# module_base.net
KiCad netlist of a schematic drawn in Altium Designer
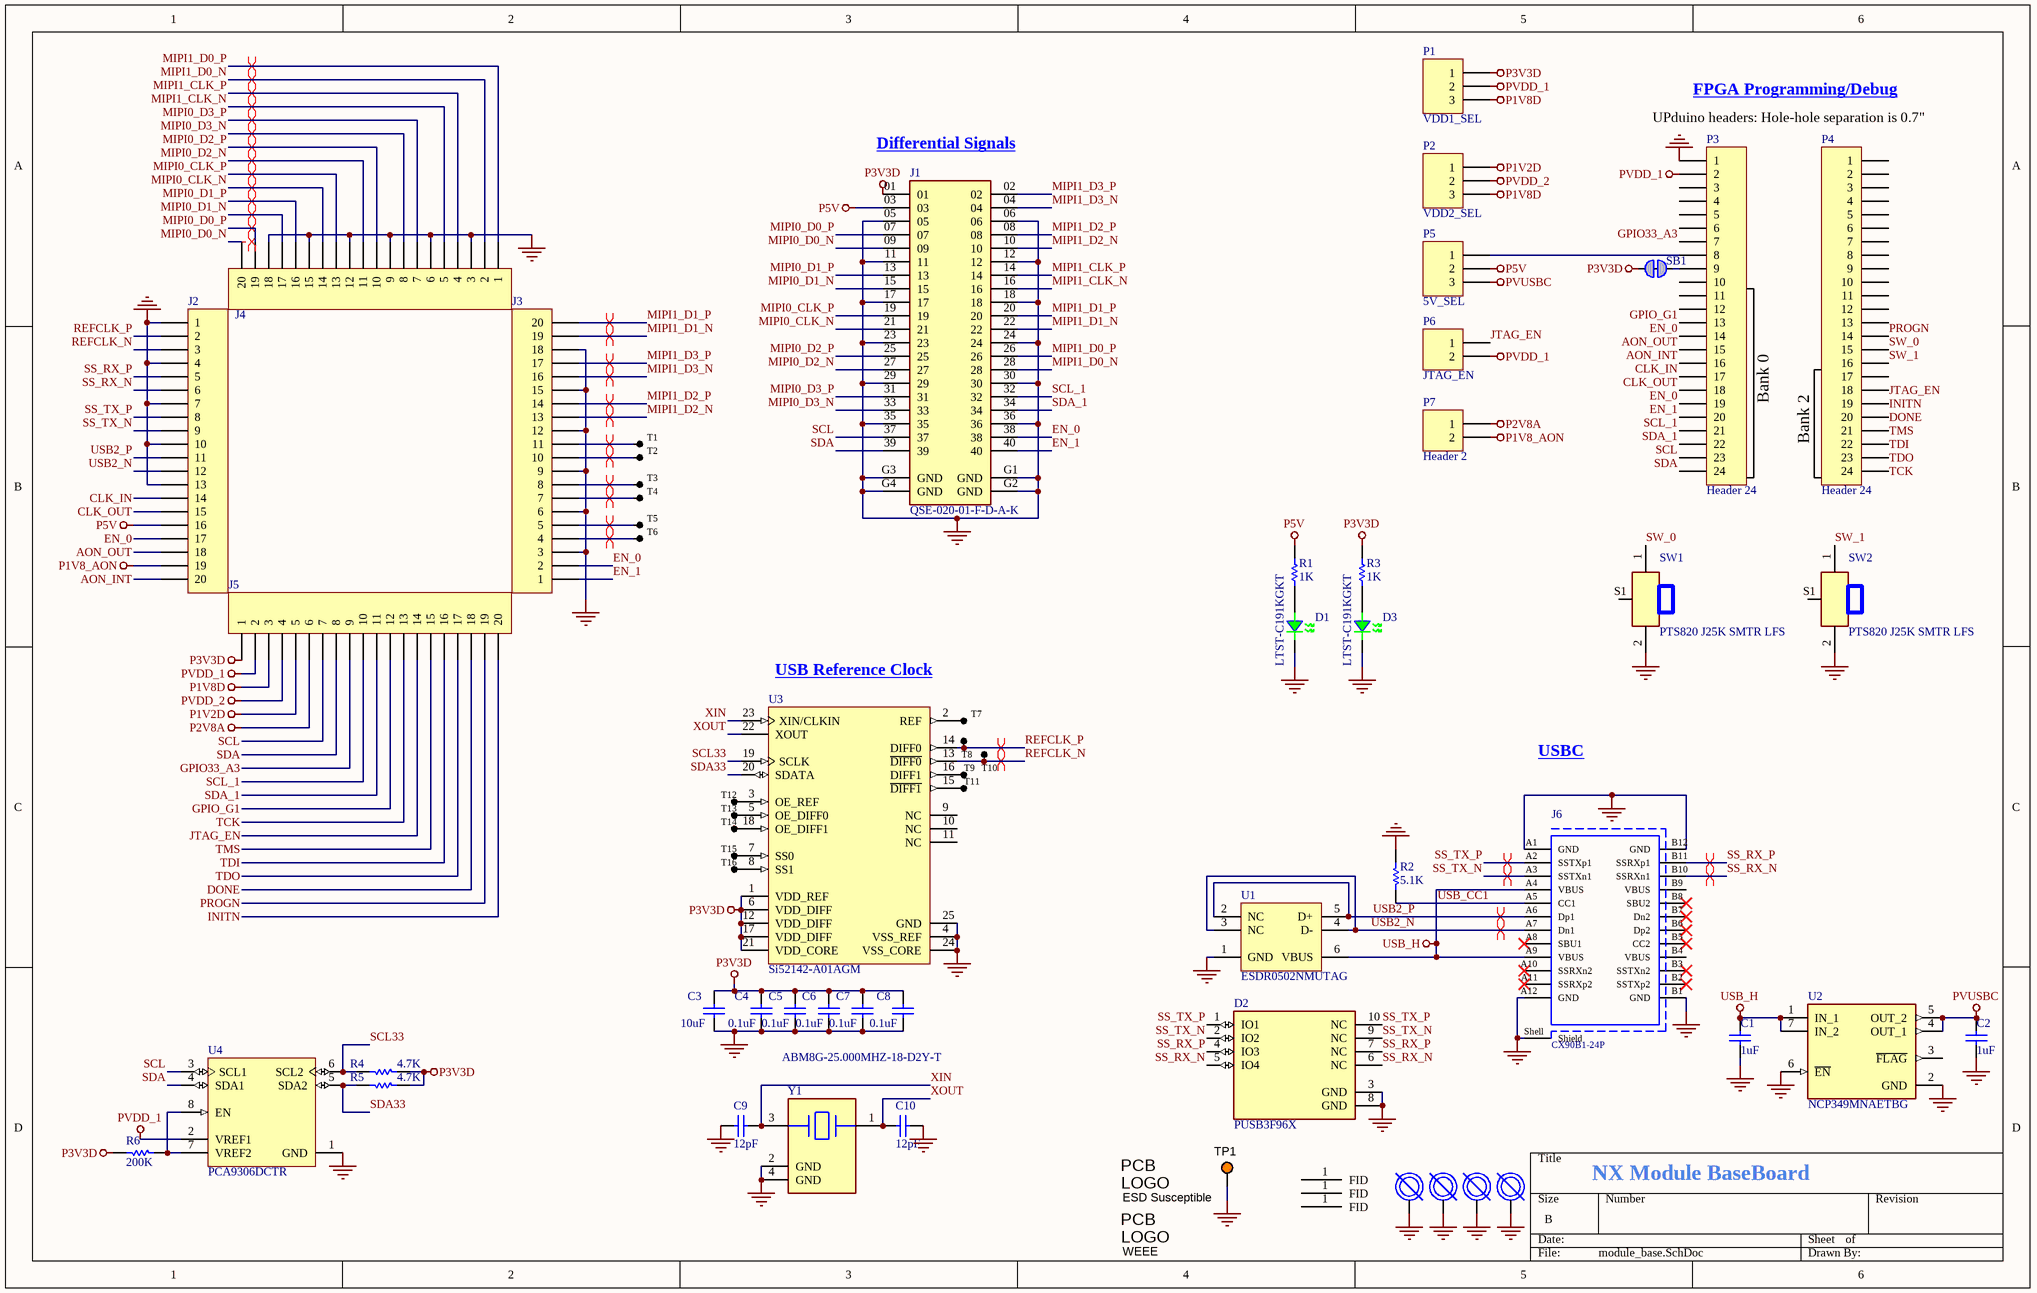
[diagram p0: module_base.SchDoc]

(export (version "E")
  (design (tool "Eeschema 10.0.6"))
  (components
    (comp (ref "BH1")
      (value "STANDOFF M2.5")
      (footprint "WE_9774010243R")
      (description "ROUND STANDOFF M2X0.4 STEEL 1MM")
      (fields
        (field (name "MANUFACTURER PART NUMBER") "9774010243R")
        (field (name "MANUFACTURER") "Würth Elektronik")
      )
      (libsource (lib "MIPI_xlator") (part "MOUNT_HOLE"))
    )
    (comp (ref "BH2")
      (value "STANDOFF M2.5")
      (footprint "WE_9774010243R")
      (description "ROUND STANDOFF M2X0.4 STEEL 1MM")
      (fields
        (field (name "MANUFACTURER PART NUMBER") "9774010243R")
        (field (name "MANUFACTURER") "Würth Elektronik")
      )
      (libsource (lib "MIPI_xlator") (part "MOUNT_HOLE"))
    )
    (comp (ref "BH3")
      (value "STANDOFF M2.5")
      (footprint "WE_9774010243R")
      (description "ROUND STANDOFF M2X0.4 STEEL 1MM")
      (fields
        (field (name "MANUFACTURER PART NUMBER") "9774010243R")
        (field (name "MANUFACTURER") "Würth Elektronik")
      )
      (libsource (lib "MIPI_xlator") (part "MOUNT_HOLE"))
    )
    (comp (ref "BH4")
      (value "STANDOFF M2.5")
      (footprint "WE_9774010243R")
      (description "ROUND STANDOFF M2X0.4 STEEL 1MM")
      (fields
        (field (name "MANUFACTURER PART NUMBER") "9774010243R")
        (field (name "MANUFACTURER") "Würth Elektronik")
      )
      (libsource (lib "MIPI_xlator") (part "MOUNT_HOLE"))
    )
    (comp (ref "C1")
      (value "1uF")
      (footprint "CAPC1005X55USR")
      (description "CAP CER 1UF 25V X5R 0402")
      (fields
        (field (name "MANUFACTURER PART NUMBER") "GRM155R61E105MA12D")
        (field (name "MANUFACTURER") "Murata Electronics")
      )
      (libsource (lib "Tiger_Ti180") (part "CAP CER 1UF 25V X5R 0402"))
    )
    (comp (ref "C2")
      (value "1uF")
      (footprint "CAPC1005X55USR")
      (description "CAP CER 1UF 25V X5R 0402")
      (fields
        (field (name "MANUFACTURER PART NUMBER") "GRM155R61E105MA12D")
        (field (name "MANUFACTURER") "Murata Electronics")
      )
      (libsource (lib "Tiger_Ti180") (part "CAP CER 1UF 25V X5R 0402"))
    )
    (comp (ref "C3")
      (value "10uF")
      (footprint "CAPC1005X90")
      (description "CAP CER 10UF 10V X5R 0402")
      (fields
        (field (name "MANUFACTURER PART NUMBER") "CL05A106MP8NUB8")
        (field (name "MANUFACTURER") "Samsung Electro-Mechanics")
      )
      (libsource (lib "Smart Camera") (part "Cap_1uF_X5R_10%_6V3_0402"))
    )
    (comp (ref "C4")
      (value "0.1uF")
      (footprint "CAPC0603X33N")
      (description "CAP CER 0.1UF 10V X7S 0201")
      (fields
        (field (name "MANUFACTURER PART NUMBER") "C0603X7S1A104K030BC")
        (field (name "MANUFACTURER") "TDK Corporation")
      )
      (libsource (lib "Smart Camera v2") (part "CAP CER 0.1UF 10V X7S 0201"))
    )
    (comp (ref "C5")
      (value "0.1uF")
      (footprint "CAPC0603X33N")
      (description "CAP CER 0.1UF 10V X7S 0201")
      (fields
        (field (name "MANUFACTURER PART NUMBER") "C0603X7S1A104K030BC")
        (field (name "MANUFACTURER") "TDK Corporation")
      )
      (libsource (lib "Smart Camera v2") (part "CAP CER 0.1UF 10V X7S 0201"))
    )
    (comp (ref "C6")
      (value "0.1uF")
      (footprint "CAPC0603X33N")
      (description "CAP CER 0.1UF 10V X7S 0201")
      (fields
        (field (name "MANUFACTURER PART NUMBER") "C0603X7S1A104K030BC")
        (field (name "MANUFACTURER") "TDK Corporation")
      )
      (libsource (lib "Smart Camera v2") (part "CAP CER 0.1UF 10V X7S 0201"))
    )
    (comp (ref "C7")
      (value "0.1uF")
      (footprint "CAPC0603X33N")
      (description "CAP CER 0.1UF 10V X7S 0201")
      (fields
        (field (name "MANUFACTURER PART NUMBER") "C0603X7S1A104K030BC")
        (field (name "MANUFACTURER") "TDK Corporation")
      )
      (libsource (lib "Smart Camera v2") (part "CAP CER 0.1UF 10V X7S 0201"))
    )
    (comp (ref "C8")
      (value "0.1uF")
      (footprint "CAPC0603X33N")
      (description "CAP CER 0.1UF 10V X7S 0201")
      (fields
        (field (name "MANUFACTURER PART NUMBER") "C0603X7S1A104K030BC")
        (field (name "MANUFACTURER") "TDK Corporation")
      )
      (libsource (lib "Smart Camera v2") (part "CAP CER 0.1UF 10V X7S 0201"))
    )
    (comp (ref "C9")
      (value "12pF")
      (footprint "CAPC0603X33N")
      (description "CAP CER 12PF 50V C0G 0201")
      (fields
        (field (name "MANUFACTURER PART NUMBER") "C0603C0G1H120K030BA")
        (field (name "MANUFACTURER") "TDK Corporation")
      )
      (libsource (lib "tinyAI") (part "CAP CER 12PF 50V C0G 0201"))
    )
    (comp (ref "C10")
      (value "12pF")
      (footprint "CAPC0603X33N")
      (description "CAP CER 12PF 50V C0G 0201")
      (fields
        (field (name "MANUFACTURER PART NUMBER") "C0603C0G1H120K030BA")
        (field (name "MANUFACTURER") "TDK Corporation")
      )
      (libsource (lib "tinyAI") (part "CAP CER 12PF 50V C0G 0201"))
    )
    (comp (ref "D1")
      (value "LTST-C191KGKT")
      (footprint "LED_0603")
      (description "LED GREEN CLEAR CHIP 0603 SMD")
      (fields
        (field (name "MANUFACTURER") "Lite-On Inc.")
        (field (name "MANUFACTURER PART NUMBER") "LTST-C191GKT")
      )
      (libsource (lib "Tiger_Ti180") (part "0603LED_GRN"))
    )
    (comp (ref "D2")
      (value "PUSB3F96X")
      (footprint "DFN2510A-10")
      (description "TVS DIODE 5.5VWM 4.6VC DFN2510A")
      (fields (field (name "MANUFACTURER") "Nexperia USA Inc."))
      (libsource (lib "Tiger_Ti180") (part "PUSB3F96X"))
    )
    (comp (ref "D3")
      (value "LTST-C191KGKT")
      (footprint "LED_0603")
      (description "LED GREEN CLEAR CHIP 0603 SMD")
      (fields
        (field (name "MANUFACTURER") "Lite-On Inc.")
        (field (name "MANUFACTURER PART NUMBER") "LTST-C191GKT")
      )
      (libsource (lib "Tiger_Ti180") (part "0603LED_GRN"))
    )
    (comp (ref "FID1") (value "~") (footprint "FID_040") (libsource (lib "MIPI_xlator") (part "FID")))
    (comp (ref "FID2") (value "~") (footprint "FID_040") (libsource (lib "MIPI_xlator") (part "FID")))
    (comp (ref "FID3") (value "~") (footprint "FID_040") (libsource (lib "MIPI_xlator") (part "FID")))
    (comp (ref "J1")
      (value "QSE-020-01-F-D-A-K")
      (footprint "SAMTEC_QSE-020-01-XXX-D-A-L")
      (description "Q Strip® High-Speed Ground Plane Header, 0.80mm Pitch")
      (fields
        (field (name "MANUFACTURER") "Samtec")
        (field (name "MANUFACTURER PART NUMBER") "QTE-020-01-F-D-A")
      )
      (libsource (lib "NX Module baseboard") (part "QSE-020-01-F-D-A-K"))
    )
    (comp (ref "J2")
      (value "Header 20")
      (footprint "HDR1X20_CASTELLATED")
      (description "Header, 20-Pin")
      (fields (field (name "PUBLISHER") "Altium Limited"))
      (libsource (lib "") (part "Header 20_2"))
    )
    (comp (ref "J3")
      (value "Header 20")
      (footprint "HDR1X20_CASTELLATED")
      (description "Header, 20-Pin")
      (fields (field (name "PUBLISHER") "Altium Limited"))
      (libsource (lib "") (part "Header 20_1"))
    )
    (comp (ref "J4")
      (value "Header 20")
      (footprint "HDR1X20_CASTELLATED")
      (description "Header, 20-Pin")
      (fields (field (name "PUBLISHER") "Altium Limited"))
      (libsource (lib "") (part "Header 20_3"))
    )
    (comp (ref "J5")
      (value "Header 20")
      (footprint "HDR1X20_CASTELLATED")
      (description "Header, 20-Pin")
      (fields (field (name "PUBLISHER") "Altium Limited"))
      (libsource (lib "NX Module") (part "Header 20"))
    )
    (comp (ref "J6")
      (value "CX90B1-24P")
      (footprint "HRS_CX90B1-24P")
      (description "CONN RCP USB3.1 TYPEC 24P SMD RA")
      (fields (field (name "MANUFACTURER") "Hirose Electric Co Ltd"))
      (libsource (lib "Tiger_Ti180") (part "USB 3.1_HRS_CX90B1-24P"))
    )
    (comp (ref "Logo1")
      (value "WEEE")
      (footprint "WEEE_Minimum")
      (description "WEEE logo")
      (libsource (lib "MIPI_xlator") (part "Logo WEEE"))
    )
    (comp (ref "Logo2")
      (value "ESD Susceptible")
      (footprint "ESD_Overlay_Medium")
      (description "ESD Susceptible Symbol")
      (fields (field (name "PUBLISHER") "Texas Instruments") (field (name "SYMBOLCREATOR") "a0412235"))
      (libsource (lib "MIPI_xlator") (part "Logo ESD"))
    )
    (comp (ref "P1")
      (value "VDD1_SEL")
      (footprint "HDR1X3")
      (description "Header, 3-Pin")
      (fields (field (name "PUBLISHER") "Altium Limited"))
      (libsource (lib "Miscellaneous Connectors") (part "Header 3"))
    )
    (comp (ref "P2")
      (value "VDD2_SEL")
      (footprint "HDR1X3")
      (description "Header, 3-Pin")
      (fields (field (name "PUBLISHER") "Altium Limited"))
      (libsource (lib "Miscellaneous Connectors") (part "Header 3"))
    )
    (comp (ref "P3")
      (value "Header 24")
      (footprint "HDR1X24")
      (description "Header, 24-Pin")
      (fields (field (name "PUBLISHER") "Altium Limited"))
      (libsource (lib "") (part "Header 24_1"))
    )
    (comp (ref "P4")
      (value "Header 24")
      (footprint "HDR1X24")
      (description "Header, 24-Pin")
      (fields (field (name "PUBLISHER") "Altium Limited"))
      (libsource (lib "Miscellaneous Connectors") (part "Header 24"))
    )
    (comp (ref "P5")
      (value "5V_SEL")
      (footprint "HDR1X3")
      (description "Header, 3-Pin")
      (fields (field (name "PUBLISHER") "Altium Limited"))
      (libsource (lib "Miscellaneous Connectors") (part "Header 3"))
    )
    (comp (ref "P6")
      (value "JTAG_EN")
      (footprint "HDR1X2")
      (description "Header, 2-Pin")
      (fields (field (name "PUBLISHER") "Altium Limited"))
      (libsource (lib "Miscellaneous Connectors") (part "Header 2"))
    )
    (comp (ref "P7")
      (value "Header 2")
      (footprint "HDR1X2")
      (description "Header, 2-Pin")
      (fields (field (name "PUBLISHER") "Altium Limited"))
      (libsource (lib "Miscellaneous Connectors") (part "Header 2"))
    )
    (comp (ref "R1")
      (value "1K")
      (footprint "RESC1005X40USR")
      (description "RES SMD 1K OHM 1% 1/16W 0402")
      (fields
        (field (name "MANUFACTURER") "YAGEO")
        (field (name "MANUFACTURER PART NUMBER") "RC0402FR-071KL")
      )
      (libsource (lib "Tiger_Ti180") (part "RES 1K OHM 1% 1/16W 0402"))
    )
    (comp (ref "R2")
      (value "5.1K")
      (footprint "RESC1005X40USR")
      (description "RES SMD 5.1K OHM 1% 1/16W 0402")
      (fields
        (field (name "MANUFACTURER") "YAGEO")
        (field (name "MANUFACTURER PART NUMBER") "RC0402FR-075K1L")
      )
      (libsource (lib "Tiger_Ti180") (part "RES 5.1K OHM 1% 1/16W 0402"))
    )
    (comp (ref "R3")
      (value "1K")
      (footprint "RESC1005X40USR")
      (description "RES SMD 1K OHM 1% 1/16W 0402")
      (fields
        (field (name "MANUFACTURER") "YAGEO")
        (field (name "MANUFACTURER PART NUMBER") "RC0402FR-071KL")
      )
      (libsource (lib "Tiger_Ti180") (part "RES 1K OHM 1% 1/16W 0402"))
    )
    (comp (ref "R4")
      (value "4.7K")
      (footprint "RESC0603X26N")
      (description "RES 4.7K OHM 1% 1/20W 0201")
      (fields
        (field (name "MANUFACTURER") "Yageo")
        (field (name "MANUFACTURER PART NUMBER") "RC0201FR-074K7L")
      )
      (libsource (lib "Smart Camera v2") (part "RES 4.7K OHM 1% 1/20W 0201"))
    )
    (comp (ref "R5")
      (value "4.7K")
      (footprint "RESC0603X26N")
      (description "RES 4.7K OHM 1% 1/20W 0201")
      (fields
        (field (name "MANUFACTURER") "Yageo")
        (field (name "MANUFACTURER PART NUMBER") "RC0201FR-074K7L")
      )
      (libsource (lib "Smart Camera v2") (part "RES 4.7K OHM 1% 1/20W 0201"))
    )
    (comp (ref "R6")
      (value "200K")
      (footprint "RESC1005X40USR")
      (description "RES SMD 200K OHM 1% 1/16W 0402")
      (fields
        (field (name "MANUFACTURER") "Stackpole Electronics Inc")
        (field (name "MANUFACTURER PART NUMBER") "RMCF0402FT200K")
      )
      (libsource (lib "MCD_Temp_LBE") (part "Res_10K_1%_0402"))
    )
    (comp (ref "SB1")
      (value "Solderbridge")
      (footprint "Solderbridge_Shorted")
      (description "Shorted Solderbridge")
      (fields
        (field (name "PART NUMBER") "Solderbridge Shorted")
        (field (name "PUBLISHER") "Nordic Semiconductor")
      )
      (libsource (lib "Tiger_Ti180") (part "Solderbridge Shorted"))
    )
    (comp (ref "SW1")
      (value "PTS820 J25K SMTR LFS")
      (footprint "PTS820J25MSMTRLFS")
      (description "SWITCH TACTILE SPST-NO 0.05A 12V")
      (fields (field (name "MANUFACTURER") "C&K"))
      (libsource (lib "Tiger_Ti180") (part "SPST_NO"))
    )
    (comp (ref "SW2")
      (value "PTS820 J25K SMTR LFS")
      (footprint "PTS820J25MSMTRLFS")
      (description "SWITCH TACTILE SPST-NO 0.05A 12V")
      (fields (field (name "MANUFACTURER") "C&K"))
      (libsource (lib "Tiger_Ti180") (part "SPST_NO"))
    )
    (comp (ref "T1")
      (value "~")
      (footprint "TP 1mm")
      (description "test point")
      (libsource (lib "Smart Camera") (part "TP_S"))
    )
    (comp (ref "T2")
      (value "~")
      (footprint "TP 1mm")
      (description "test point")
      (libsource (lib "Smart Camera") (part "TP_S"))
    )
    (comp (ref "T3")
      (value "~")
      (footprint "TP 1mm")
      (description "test point")
      (libsource (lib "Smart Camera") (part "TP_S"))
    )
    (comp (ref "T4")
      (value "~")
      (footprint "TP 1mm")
      (description "test point")
      (libsource (lib "Smart Camera") (part "TP_S"))
    )
    (comp (ref "T5")
      (value "~")
      (footprint "TP 1mm")
      (description "test point")
      (libsource (lib "Smart Camera") (part "TP_S"))
    )
    (comp (ref "T6")
      (value "~")
      (footprint "TP 1mm")
      (description "test point")
      (libsource (lib "Smart Camera") (part "TP_S"))
    )
    (comp (ref "T7")
      (value "~")
      (footprint "TP 1mm")
      (description "test point")
      (libsource (lib "Smart Camera") (part "TP_S"))
    )
    (comp (ref "T8")
      (value "~")
      (footprint "TP 1mm")
      (description "test point")
      (libsource (lib "Smart Camera") (part "TP_S"))
    )
    (comp (ref "T9")
      (value "~")
      (footprint "TP 1mm")
      (description "test point")
      (libsource (lib "Smart Camera") (part "TP_S"))
    )
    (comp (ref "T10")
      (value "~")
      (footprint "TP 1mm")
      (description "test point")
      (libsource (lib "Smart Camera") (part "TP_S"))
    )
    (comp (ref "T11")
      (value "~")
      (footprint "TP 1mm")
      (description "test point")
      (libsource (lib "Smart Camera") (part "TP_S"))
    )
    (comp (ref "T12")
      (value "~")
      (footprint "TP 1mm")
      (description "test point")
      (libsource (lib "Smart Camera") (part "TP_S"))
    )
    (comp (ref "T13")
      (value "~")
      (footprint "TP 1mm")
      (description "test point")
      (libsource (lib "Smart Camera") (part "TP_S"))
    )
    (comp (ref "T14")
      (value "~")
      (footprint "TP 1mm")
      (description "test point")
      (libsource (lib "Smart Camera") (part "TP_S"))
    )
    (comp (ref "T15")
      (value "~")
      (footprint "TP 1mm")
      (description "test point")
      (libsource (lib "Smart Camera") (part "TP_S"))
    )
    (comp (ref "T16")
      (value "~")
      (footprint "TP 1mm")
      (description "test point")
      (libsource (lib "Smart Camera") (part "TP_S"))
    )
    (comp (ref "TP1")
      (value "5019")
      (footprint "TP380X203")
      (description "PC TEST POINT MINIATURE")
      (fields (field (name "MANUFACTURER") "Keystone Electronics"))
      (libsource (lib "MIPI_xlator") (part "5019"))
    )
    (comp (ref "U1")
      (value "ESDR0502NMUTAG")
      (footprint "ONSC-UDFN-6-517AA-01_V")
      (description "TVS DIODE 5.5VWM 6UDFN")
      (fields (field (name "MANUFACTURER") "ON Semiconductor"))
      (libsource (lib "Tiger_Ti180") (part "ONSC-ESDR0502N-UDFN-6-517AA-01"))
    )
    (comp (ref "U2")
      (value "NCP349MNAETBG")
      (footprint "SON50P200X160X100-7N-D")
      (description "IC CTLR OVP 28V W/NMOS 6-DFN")
      (fields (field (name "MANUFACTURER") "ON Semiconductor"))
      (libsource (lib "Tiger_Ti180") (part "NCP349MNAETBG"))
    )
    (comp (ref "U3")
      (value "Si52142-A01AGM")
      (footprint "SLAB-QFN-24-2700x2700TP_M")
      (fields (field (name "MANUFACTURER") "Silicon Labs"))
      (libsource (lib "Altium Content Vault") (part "SLAB-Si52142-QFN-24-25"))
    )
    (comp (ref "U4")
      (value "PCA9306DCTR")
      (footprint "SOP65P400X130-8N")
      (fields (field (name "MANUFACTURER") "Texas Instruments"))
      (libsource (lib "NX Module") (part "TI-PCA9306-SM8_DCT-8"))
    )
    (comp (ref "Y1")
      (value "ABM8G-25.000MHZ-18-D2Y-T")
      (footprint "XTAL_ABM8G3225X10")
      (description "Crystal 25MHz ±20ppm (Tol) ±30ppm (Stability) 18pF FUND 60Ohm 4-Pin Ultra Mini-CSMD T/R")
      (fields (field (name "MANUFACTURER") "Abracon") (field (name "TOLERANCE") "20ppm"))
      (libsource (lib "NX Module") (part "48e526d86b7f2615d98721063c72f49"))
    )
  )
  (nets
    (net (code "1") (name "/AON_INT") (class "Default")
      (node (ref "J2") (pin "20") (pinfunction "20_20") (pintype "passive"))
      (node (ref "P3") (pin "16") (pinfunction "16_16") (pintype "passive"))
    )
    (net (code "2") (name "/AON_OUT") (class "Default")
      (node (ref "J2") (pin "18") (pinfunction "18_18") (pintype "passive"))
      (node (ref "P3") (pin "15") (pinfunction "15_15") (pintype "passive"))
    )
    (net (code "3") (name "/CLK_IN") (class "Default")
      (node (ref "J2") (pin "14") (pinfunction "14_14") (pintype "passive"))
      (node (ref "P3") (pin "17") (pinfunction "17_17") (pintype "passive"))
    )
    (net (code "4") (name "/CLK_OUT") (class "Default")
      (node (ref "J2") (pin "15") (pinfunction "15_15") (pintype "passive"))
      (node (ref "P3") (pin "18") (pinfunction "18_18") (pintype "passive"))
    )
    (net (code "5") (name "/DONE") (class "Default")
      (node (ref "J5") (pin "18") (pinfunction "18_18") (pintype "passive"))
      (node (ref "P4") (pin "20") (pinfunction "20_20") (pintype "passive"))
    )
    (net (code "6") (name "/EN_0") (class "Default")
      (node (ref "J1") (pin "38") (pinfunction "38_38") (pintype "passive"))
      (node (ref "J2") (pin "17") (pinfunction "17_17") (pintype "passive"))
      (node (ref "J3") (pin "2") (pinfunction "2_2") (pintype "passive"))
      (node (ref "P3") (pin "14") (pinfunction "14_14") (pintype "passive"))
      (node (ref "P3") (pin "19") (pinfunction "19_19") (pintype "passive"))
    )
    (net (code "7") (name "/EN_1") (class "Default")
      (node (ref "J1") (pin "40") (pinfunction "40_40") (pintype "passive"))
      (node (ref "J3") (pin "1") (pinfunction "1_1") (pintype "passive"))
      (node (ref "P3") (pin "20") (pinfunction "20_20") (pintype "passive"))
    )
    (net (code "8") (name "/GPIO33_A3") (class "Default")
      (node (ref "J5") (pin "9") (pinfunction "9_9") (pintype "passive"))
      (node (ref "P3") (pin "7") (pinfunction "7_7") (pintype "passive"))
    )
    (net (code "9") (name "/GPIO_G1") (class "Default")
      (node (ref "J5") (pin "12") (pinfunction "12_12") (pintype "passive"))
      (node (ref "P3") (pin "13") (pinfunction "13_13") (pintype "passive"))
    )
    (net (code "10") (name "/INITN") (class "Default")
      (node (ref "J5") (pin "20") (pinfunction "20_20") (pintype "passive"))
      (node (ref "P4") (pin "19") (pinfunction "19_19") (pintype "passive"))
    )
    (net (code "11") (name "/JTAG_EN") (class "Default")
      (node (ref "J5") (pin "14") (pinfunction "14_14") (pintype "passive"))
      (node (ref "P4") (pin "18") (pinfunction "18_18") (pintype "passive"))
      (node (ref "P6") (pin "1") (pinfunction "1_1") (pintype "passive"))
    )
    (net (code "12") (name "/MIPI0_CLK_N") (class "Default")
      (node (ref "J1") (pin "21") (pinfunction "21_21") (pintype "passive"))
      (node (ref "J4") (pin "14") (pinfunction "14_14") (pintype "passive"))
    )
    (net (code "13") (name "/MIPI0_CLK_P") (class "Default")
      (node (ref "J1") (pin "19") (pinfunction "19_19") (pintype "passive"))
      (node (ref "J4") (pin "13") (pinfunction "13_13") (pintype "passive"))
    )
    (net (code "14") (name "/MIPI0_D0_N") (class "Default")
      (node (ref "J1") (pin "09") (pinfunction "09_09") (pintype "passive"))
      (node (ref "J4") (pin "20") (pinfunction "20_20") (pintype "passive"))
    )
    (net (code "15") (name "/MIPI0_D0_P") (class "Default")
      (node (ref "J1") (pin "07") (pinfunction "07_07") (pintype "passive"))
      (node (ref "J4") (pin "19") (pinfunction "19_19") (pintype "passive"))
    )
    (net (code "16") (name "/MIPI0_D1_N") (class "Default")
      (node (ref "J1") (pin "15") (pinfunction "15_15") (pintype "passive"))
      (node (ref "J4") (pin "17") (pinfunction "17_17") (pintype "passive"))
    )
    (net (code "17") (name "/MIPI0_D1_P") (class "Default")
      (node (ref "J1") (pin "13") (pinfunction "13_13") (pintype "passive"))
      (node (ref "J4") (pin "16") (pinfunction "16_16") (pintype "passive"))
    )
    (net (code "18") (name "/MIPI0_D2_N") (class "Default")
      (node (ref "J1") (pin "27") (pinfunction "27_27") (pintype "passive"))
      (node (ref "J4") (pin "11") (pinfunction "11_11") (pintype "passive"))
    )
    (net (code "19") (name "/MIPI0_D2_P") (class "Default")
      (node (ref "J1") (pin "25") (pinfunction "25_25") (pintype "passive"))
      (node (ref "J4") (pin "10") (pinfunction "10_10") (pintype "passive"))
    )
    (net (code "20") (name "/MIPI0_D3_N") (class "Default")
      (node (ref "J1") (pin "33") (pinfunction "33_33") (pintype "passive"))
      (node (ref "J4") (pin "8") (pinfunction "8_8") (pintype "passive"))
    )
    (net (code "21") (name "/MIPI0_D3_P") (class "Default")
      (node (ref "J1") (pin "31") (pinfunction "31_31") (pintype "passive"))
      (node (ref "J4") (pin "7") (pinfunction "7_7") (pintype "passive"))
    )
    (net (code "22") (name "/MIPI1_CLK_N") (class "Default")
      (node (ref "J1") (pin "16") (pinfunction "16_16") (pintype "passive"))
      (node (ref "J4") (pin "5") (pinfunction "5_5") (pintype "passive"))
    )
    (net (code "23") (name "/MIPI1_CLK_P") (class "Default")
      (node (ref "J1") (pin "14") (pinfunction "14_14") (pintype "passive"))
      (node (ref "J4") (pin "4") (pinfunction "4_4") (pintype "passive"))
    )
    (net (code "24") (name "/MIPI1_D0_N") (class "Default")
      (node (ref "J1") (pin "28") (pinfunction "28_28") (pintype "passive"))
      (node (ref "J4") (pin "2") (pinfunction "2_2") (pintype "passive"))
    )
    (net (code "25") (name "/MIPI1_D0_P") (class "Default")
      (node (ref "J1") (pin "26") (pinfunction "26_26") (pintype "passive"))
      (node (ref "J4") (pin "1") (pinfunction "1_1") (pintype "passive"))
    )
    (net (code "26") (name "/MIPI1_D1_N") (class "Default")
      (node (ref "J1") (pin "22") (pinfunction "22_22") (pintype "passive"))
      (node (ref "J3") (pin "19") (pinfunction "19_19") (pintype "passive"))
    )
    (net (code "27") (name "/MIPI1_D1_P") (class "Default")
      (node (ref "J1") (pin "20") (pinfunction "20_20") (pintype "passive"))
      (node (ref "J3") (pin "20") (pinfunction "20_20") (pintype "passive"))
    )
    (net (code "28") (name "/MIPI1_D2_N") (class "Default")
      (node (ref "J1") (pin "10") (pinfunction "10_10") (pintype "passive"))
      (node (ref "J3") (pin "13") (pinfunction "13_13") (pintype "passive"))
    )
    (net (code "29") (name "/MIPI1_D2_P") (class "Default")
      (node (ref "J1") (pin "08") (pinfunction "08_08") (pintype "passive"))
      (node (ref "J3") (pin "14") (pinfunction "14_14") (pintype "passive"))
    )
    (net (code "30") (name "/MIPI1_D3_N") (class "Default")
      (node (ref "J1") (pin "04") (pinfunction "04_04") (pintype "passive"))
      (node (ref "J3") (pin "16") (pinfunction "16_16") (pintype "passive"))
    )
    (net (code "31") (name "/MIPI1_D3_P") (class "Default")
      (node (ref "J1") (pin "02") (pinfunction "02_02") (pintype "passive"))
      (node (ref "J3") (pin "17") (pinfunction "17_17") (pintype "passive"))
    )
    (net (code "32") (name "/PROGN") (class "Default")
      (node (ref "J5") (pin "19") (pinfunction "19_19") (pintype "passive"))
      (node (ref "P4") (pin "14") (pinfunction "14_14") (pintype "passive"))
    )
    (net (code "33") (name "/REFCLK_N") (class "Default")
      (node (ref "J2") (pin "3") (pinfunction "3_3") (pintype "passive"))
      (node (ref "T10") (pin "1") (pintype "passive"))
      (node (ref "U3") (pin "13") (pinfunction "~{DIFF0}_13") (pintype "output"))
    )
    (net (code "34") (name "/REFCLK_P") (class "Default")
      (node (ref "J2") (pin "2") (pinfunction "2_2") (pintype "passive"))
      (node (ref "T8") (pin "1") (pintype "passive"))
      (node (ref "U3") (pin "14") (pinfunction "DIFF0_14") (pintype "output"))
    )
    (net (code "35") (name "/SCL") (class "Default")
      (node (ref "J1") (pin "37") (pinfunction "37_37") (pintype "passive"))
      (node (ref "J5") (pin "7") (pinfunction "7_7") (pintype "passive"))
      (node (ref "P3") (pin "23") (pinfunction "23_23") (pintype "passive"))
      (node (ref "U4") (pin "3") (pinfunction "SCL1_3") (pintype "bidirectional"))
    )
    (net (code "36") (name "/SCL33") (class "Default")
      (node (ref "R4") (pin "1") (pinfunction "1_1") (pintype "passive"))
      (node (ref "U3") (pin "19") (pinfunction "SCLK_19") (pintype "input"))
      (node (ref "U4") (pin "6") (pinfunction "SCL2_6") (pintype "bidirectional"))
    )
    (net (code "37") (name "/SCL_1") (class "Default")
      (node (ref "J1") (pin "32") (pinfunction "32_32") (pintype "passive"))
      (node (ref "J5") (pin "10") (pinfunction "10_10") (pintype "passive"))
      (node (ref "P3") (pin "21") (pinfunction "21_21") (pintype "passive"))
    )
    (net (code "38") (name "/SDA") (class "Default")
      (node (ref "J1") (pin "39") (pinfunction "39_39") (pintype "passive"))
      (node (ref "J5") (pin "8") (pinfunction "8_8") (pintype "passive"))
      (node (ref "P3") (pin "24") (pinfunction "24_24") (pintype "passive"))
      (node (ref "U4") (pin "4") (pinfunction "SDA1_4") (pintype "bidirectional"))
    )
    (net (code "39") (name "/SDA33") (class "Default")
      (node (ref "R5") (pin "1") (pinfunction "1_1") (pintype "passive"))
      (node (ref "U3") (pin "20") (pinfunction "SDATA_20") (pintype "bidirectional"))
      (node (ref "U4") (pin "5") (pinfunction "SDA2_5") (pintype "bidirectional"))
    )
    (net (code "40") (name "/SDA_1") (class "Default")
      (node (ref "J1") (pin "34") (pinfunction "34_34") (pintype "passive"))
      (node (ref "J5") (pin "11") (pinfunction "11_11") (pintype "passive"))
      (node (ref "P3") (pin "22") (pinfunction "22_22") (pintype "passive"))
    )
    (net (code "41") (name "/SS_RX_N") (class "Default")
      (node (ref "D2") (pin "5") (pinfunction "IO4_5") (pintype "bidirectional"))
      (node (ref "D2") (pin "6") (pinfunction "NC_6") (pintype "passive"))
      (node (ref "J2") (pin "6") (pinfunction "6_6") (pintype "passive"))
      (node (ref "J6") (pin "B10") (pinfunction "SSRXn1_B10") (pintype "passive"))
    )
    (net (code "42") (name "/SS_RX_P") (class "Default")
      (node (ref "D2") (pin "4") (pinfunction "IO3_4") (pintype "bidirectional"))
      (node (ref "D2") (pin "7") (pinfunction "NC_7") (pintype "passive"))
      (node (ref "J2") (pin "5") (pinfunction "5_5") (pintype "passive"))
      (node (ref "J6") (pin "B11") (pinfunction "SSRXp1_B11") (pintype "passive"))
    )
    (net (code "43") (name "/SS_TX_N") (class "Default")
      (node (ref "D2") (pin "2") (pinfunction "IO2_2") (pintype "bidirectional"))
      (node (ref "D2") (pin "9") (pinfunction "NC_9") (pintype "passive"))
      (node (ref "J2") (pin "9") (pinfunction "9_9") (pintype "passive"))
      (node (ref "J6") (pin "A3") (pinfunction "SSTXn1_A3") (pintype "passive"))
    )
    (net (code "44") (name "/SS_TX_P") (class "Default")
      (node (ref "D2") (pin "1") (pinfunction "IO1_1") (pintype "bidirectional"))
      (node (ref "D2") (pin "10") (pinfunction "NC_10") (pintype "passive"))
      (node (ref "J2") (pin "8") (pinfunction "8_8") (pintype "passive"))
      (node (ref "J6") (pin "A2") (pinfunction "SSTXp1_A2") (pintype "passive"))
    )
    (net (code "45") (name "/SW_0") (class "Default")
      (node (ref "P4") (pin "15") (pinfunction "15_15") (pintype "passive"))
      (node (ref "SW1") (pin "1") (pinfunction "1_1") (pintype "passive"))
    )
    (net (code "46") (name "/SW_1") (class "Default")
      (node (ref "P4") (pin "16") (pinfunction "16_16") (pintype "passive"))
      (node (ref "SW2") (pin "1") (pinfunction "1_1") (pintype "passive"))
    )
    (net (code "47") (name "/TCK") (class "Default")
      (node (ref "J5") (pin "13") (pinfunction "13_13") (pintype "passive"))
      (node (ref "P4") (pin "24") (pinfunction "24_24") (pintype "passive"))
    )
    (net (code "48") (name "/TDI") (class "Default")
      (node (ref "J5") (pin "16") (pinfunction "16_16") (pintype "passive"))
      (node (ref "P4") (pin "22") (pinfunction "22_22") (pintype "passive"))
    )
    (net (code "49") (name "/TDO") (class "Default")
      (node (ref "J5") (pin "17") (pinfunction "17_17") (pintype "passive"))
      (node (ref "P4") (pin "23") (pinfunction "23_23") (pintype "passive"))
    )
    (net (code "50") (name "/TMS") (class "Default")
      (node (ref "J5") (pin "15") (pinfunction "15_15") (pintype "passive"))
      (node (ref "P4") (pin "21") (pinfunction "21_21") (pintype "passive"))
    )
    (net (code "51") (name "/USB2_N") (class "Default")
      (node (ref "J2") (pin "12") (pinfunction "12_12") (pintype "passive"))
      (node (ref "J6") (pin "A7") (pinfunction "Dn1_A7") (pintype "passive"))
      (node (ref "U1") (pin "3") (pinfunction "NC_3") (pintype "passive"))
      (node (ref "U1") (pin "4") (pinfunction "D-_4") (pintype "passive"))
    )
    (net (code "52") (name "/USB2_P") (class "Default")
      (node (ref "J2") (pin "11") (pinfunction "11_11") (pintype "passive"))
      (node (ref "J6") (pin "A6") (pinfunction "Dp1_A6") (pintype "passive"))
      (node (ref "U1") (pin "2") (pinfunction "NC_2") (pintype "passive"))
      (node (ref "U1") (pin "5") (pinfunction "D+_5") (pintype "passive"))
    )
    (net (code "53") (name "/USB_CC1") (class "Default")
      (node (ref "J6") (pin "A5") (pinfunction "CC1_A5") (pintype "passive"))
      (node (ref "R2") (pin "1") (pinfunction "1_1") (pintype "passive"))
    )
    (net (code "54") (name "/XIN") (class "Default")
      (node (ref "C9") (pin "1") (pinfunction "1_1") (pintype "passive"))
      (node (ref "U3") (pin "23") (pinfunction "XIN/CLKIN_23") (pintype "input"))
      (node (ref "Y1") (pin "3") (pinfunction "3_3") (pintype "passive"))
    )
    (net (code "55") (name "/XOUT") (class "Default")
      (node (ref "C10") (pin "1") (pinfunction "1_1") (pintype "passive"))
      (node (ref "U3") (pin "22") (pinfunction "XOUT_22") (pintype "passive"))
      (node (ref "Y1") (pin "1") (pinfunction "1_1") (pintype "passive"))
    )
    (net (code "56") (name "GND") (class "Default")
      (node (ref "BH1") (pin "1") (pinfunction "1_1") (pintype "passive"))
      (node (ref "BH2") (pin "1") (pinfunction "1_1") (pintype "passive"))
      (node (ref "BH3") (pin "1") (pinfunction "1_1") (pintype "passive"))
      (node (ref "BH4") (pin "1") (pinfunction "1_1") (pintype "passive"))
      (node (ref "C1") (pin "1") (pinfunction "1_1") (pintype "passive"))
      (node (ref "C10") (pin "2") (pinfunction "2_2") (pintype "passive"))
      (node (ref "C2") (pin "1") (pinfunction "1_1") (pintype "passive"))
      (node (ref "C3") (pin "1") (pinfunction "1_1") (pintype "passive"))
      (node (ref "C4") (pin "1") (pinfunction "1_1") (pintype "passive"))
      (node (ref "C5") (pin "1") (pinfunction "1_1") (pintype "passive"))
      (node (ref "C6") (pin "1") (pinfunction "1_1") (pintype "passive"))
      (node (ref "C7") (pin "1") (pinfunction "1_1") (pintype "passive"))
      (node (ref "C8") (pin "1") (pinfunction "1_1") (pintype "passive"))
      (node (ref "C9") (pin "2") (pinfunction "2_2") (pintype "passive"))
      (node (ref "D1") (pin "2") (pinfunction "K_2") (pintype "passive"))
      (node (ref "D2") (pin "3") (pinfunction "GND_3") (pintype "power_in"))
      (node (ref "D2") (pin "8") (pinfunction "GND_8") (pintype "power_in"))
      (node (ref "D3") (pin "2") (pinfunction "K_2") (pintype "passive"))
      (node (ref "J1") (pin "05") (pinfunction "05_05") (pintype "passive"))
      (node (ref "J1") (pin "06") (pinfunction "06_06") (pintype "passive"))
      (node (ref "J1") (pin "11") (pinfunction "11_11") (pintype "passive"))
      (node (ref "J1") (pin "12") (pinfunction "12_12") (pintype "passive"))
      (node (ref "J1") (pin "17") (pinfunction "17_17") (pintype "passive"))
      (node (ref "J1") (pin "18") (pinfunction "18_18") (pintype "passive"))
      (node (ref "J1") (pin "23") (pinfunction "23_23") (pintype "passive"))
      (node (ref "J1") (pin "24") (pinfunction "24_24") (pintype "passive"))
      (node (ref "J1") (pin "29") (pinfunction "29_29") (pintype "passive"))
      (node (ref "J1") (pin "30") (pinfunction "30_30") (pintype "passive"))
      (node (ref "J1") (pin "35") (pinfunction "35_35") (pintype "passive"))
      (node (ref "J1") (pin "36") (pinfunction "36_36") (pintype "passive"))
      (node (ref "J1") (pin "G1") (pinfunction "GND_G1") (pintype "power_in"))
      (node (ref "J1") (pin "G2") (pinfunction "GND_G2") (pintype "power_in"))
      (node (ref "J1") (pin "G3") (pinfunction "GND_G3") (pintype "power_in"))
      (node (ref "J1") (pin "G4") (pinfunction "GND_G4") (pintype "power_in"))
      (node (ref "J2") (pin "1") (pinfunction "1_1") (pintype "passive"))
      (node (ref "J2") (pin "10") (pinfunction "10_10") (pintype "passive"))
      (node (ref "J2") (pin "13") (pinfunction "13_13") (pintype "passive"))
      (node (ref "J2") (pin "4") (pinfunction "4_4") (pintype "passive"))
      (node (ref "J2") (pin "7") (pinfunction "7_7") (pintype "passive"))
      (node (ref "J3") (pin "12") (pinfunction "12_12") (pintype "passive"))
      (node (ref "J3") (pin "15") (pinfunction "15_15") (pintype "passive"))
      (node (ref "J3") (pin "18") (pinfunction "18_18") (pintype "passive"))
      (node (ref "J3") (pin "3") (pinfunction "3_3") (pintype "passive"))
      (node (ref "J3") (pin "6") (pinfunction "6_6") (pintype "passive"))
      (node (ref "J3") (pin "9") (pinfunction "9_9") (pintype "passive"))
      (node (ref "J4") (pin "12") (pinfunction "12_12") (pintype "passive"))
      (node (ref "J4") (pin "15") (pinfunction "15_15") (pintype "passive"))
      (node (ref "J4") (pin "18") (pinfunction "18_18") (pintype "passive"))
      (node (ref "J4") (pin "3") (pinfunction "3_3") (pintype "passive"))
      (node (ref "J4") (pin "6") (pinfunction "6_6") (pintype "passive"))
      (node (ref "J4") (pin "9") (pinfunction "9_9") (pintype "passive"))
      (node (ref "J6") (pin "A1") (pinfunction "GND_A1") (pintype "passive"))
      (node (ref "J6") (pin "A12") (pinfunction "GND_A12") (pintype "passive"))
      (node (ref "J6") (pin "B1") (pinfunction "GND_B1") (pintype "passive"))
      (node (ref "J6") (pin "B12") (pinfunction "GND_B12") (pintype "passive"))
      (node (ref "J6") (pin "Shell") (pinfunction "Shield_Shell") (pintype "passive"))
      (node (ref "P3") (pin "1") (pinfunction "1_1") (pintype "passive"))
      (node (ref "R2") (pin "2") (pinfunction "2_2") (pintype "passive"))
      (node (ref "SW1") (pin "2") (pinfunction "2_2") (pintype "passive"))
      (node (ref "SW2") (pin "2") (pinfunction "2_2") (pintype "passive"))
      (node (ref "TP1") (pin "1") (pinfunction "1_1") (pintype "passive"))
      (node (ref "U1") (pin "1") (pinfunction "GND_1") (pintype "power_in"))
      (node (ref "U2") (pin "2") (pinfunction "GND_2") (pintype "power_in"))
      (node (ref "U2") (pin "6") (pinfunction "~{EN}_6") (pintype "input"))
      (node (ref "U3") (pin "24") (pinfunction "VSS_CORE_24") (pintype "power_in"))
      (node (ref "U3") (pin "25") (pinfunction "GND_25") (pintype "power_in"))
      (node (ref "U3") (pin "4") (pinfunction "VSS_REF_4") (pintype "power_in"))
      (node (ref "U4") (pin "1") (pinfunction "GND_1") (pintype "power_in"))
      (node (ref "Y1") (pin "2") (pinfunction "GND_2") (pintype "power_in"))
      (node (ref "Y1") (pin "4") (pinfunction "GND_4") (pintype "power_in"))
    )
    (net (code "57") (name "Net-(D1-A)") (class "Default")
      (node (ref "D1") (pin "1") (pinfunction "A_1") (pintype "passive"))
      (node (ref "R1") (pin "2") (pinfunction "2_2") (pintype "passive"))
    )
    (net (code "58") (name "Net-(D3-A)") (class "Default")
      (node (ref "D3") (pin "1") (pinfunction "A_1") (pintype "passive"))
      (node (ref "R3") (pin "2") (pinfunction "2_2") (pintype "passive"))
    )
    (net (code "59") (name "Net-(J3-Pad4)") (class "Default")
      (node (ref "J3") (pin "4") (pinfunction "4_4") (pintype "passive"))
      (node (ref "T6") (pin "1") (pintype "passive"))
    )
    (net (code "60") (name "Net-(J3-Pad5)") (class "Default")
      (node (ref "J3") (pin "5") (pinfunction "5_5") (pintype "passive"))
      (node (ref "T5") (pin "1") (pintype "passive"))
    )
    (net (code "61") (name "Net-(J3-Pad7)") (class "Default")
      (node (ref "J3") (pin "7") (pinfunction "7_7") (pintype "passive"))
      (node (ref "T4") (pin "1") (pintype "passive"))
    )
    (net (code "62") (name "Net-(J3-Pad8)") (class "Default")
      (node (ref "J3") (pin "8") (pinfunction "8_8") (pintype "passive"))
      (node (ref "T3") (pin "1") (pintype "passive"))
    )
    (net (code "63") (name "Net-(J3-Pad10)") (class "Default")
      (node (ref "J3") (pin "10") (pinfunction "10_10") (pintype "passive"))
      (node (ref "T2") (pin "1") (pintype "passive"))
    )
    (net (code "64") (name "Net-(J3-Pad11)") (class "Default")
      (node (ref "J3") (pin "11") (pinfunction "11_11") (pintype "passive"))
      (node (ref "T1") (pin "1") (pintype "passive"))
    )
    (net (code "65") (name "Net-(P3-Pad8)") (class "Default")
      (node (ref "P3") (pin "8") (pinfunction "8_8") (pintype "passive"))
      (node (ref "P5") (pin "1") (pinfunction "1_1") (pintype "passive"))
    )
    (net (code "66") (name "Net-(SB1-1)") (class "Default")
      (node (ref "P3") (pin "9") (pinfunction "9_9") (pintype "passive"))
      (node (ref "SB1") (pin "2") (pinfunction "1_2") (pintype "passive"))
    )
    (net (code "67") (name "Net-(U3-DIFF1)") (class "Default")
      (node (ref "T9") (pin "1") (pintype "passive"))
      (node (ref "U3") (pin "16") (pinfunction "DIFF1_16") (pintype "output"))
    )
    (net (code "68") (name "Net-(U3-OE_DIFF0)") (class "Default")
      (node (ref "T13") (pin "1") (pintype "passive"))
      (node (ref "U3") (pin "5") (pinfunction "OE_DIFF0_5") (pintype "input"))
    )
    (net (code "69") (name "Net-(U3-OE_DIFF1)") (class "Default")
      (node (ref "T14") (pin "1") (pintype "passive"))
      (node (ref "U3") (pin "18") (pinfunction "OE_DIFF1_18") (pintype "input"))
    )
    (net (code "70") (name "Net-(U3-OE_REF)") (class "Default")
      (node (ref "T12") (pin "1") (pintype "passive"))
      (node (ref "U3") (pin "3") (pinfunction "OE_REF_3") (pintype "input"))
    )
    (net (code "71") (name "Net-(U3-REF)") (class "Default")
      (node (ref "T7") (pin "1") (pintype "passive"))
      (node (ref "U3") (pin "2") (pinfunction "REF_2") (pintype "output"))
    )
    (net (code "72") (name "Net-(U3-SS0)") (class "Default")
      (node (ref "T15") (pin "1") (pintype "passive"))
      (node (ref "U3") (pin "7") (pinfunction "SS0_7") (pintype "input"))
    )
    (net (code "73") (name "Net-(U3-SS1)") (class "Default")
      (node (ref "T16") (pin "1") (pintype "passive"))
      (node (ref "U3") (pin "8") (pinfunction "SS1_8") (pintype "input"))
    )
    (net (code "74") (name "Net-(U3-~{DIFF1})") (class "Default")
      (node (ref "T11") (pin "1") (pintype "passive"))
      (node (ref "U3") (pin "15") (pinfunction "~{DIFF1}_15") (pintype "output"))
    )
    (net (code "75") (name "Net-(U4-EN)") (class "Default")
      (node (ref "R6") (pin "1") (pinfunction "1_1") (pintype "passive"))
      (node (ref "U4") (pin "7") (pinfunction "VREF2_7") (pintype "power_in"))
      (node (ref "U4") (pin "8") (pinfunction "EN_8") (pintype "input"))
    )
    (net (code "76") (name "P1V2D") (class "Default")
      (node (ref "J5") (pin "5") (pinfunction "5_5") (pintype "passive"))
      (node (ref "P2") (pin "1") (pinfunction "1_1") (pintype "passive"))
    )
    (net (code "77") (name "P1V8D") (class "Default")
      (node (ref "J5") (pin "3") (pinfunction "3_3") (pintype "passive"))
      (node (ref "P1") (pin "3") (pinfunction "3_3") (pintype "passive"))
      (node (ref "P2") (pin "3") (pinfunction "3_3") (pintype "passive"))
    )
    (net (code "78") (name "P1V8_AON") (class "Default")
      (node (ref "J2") (pin "19") (pinfunction "19_19") (pintype "passive"))
      (node (ref "P7") (pin "2") (pinfunction "2_2") (pintype "passive"))
    )
    (net (code "79") (name "P2V8A") (class "Default")
      (node (ref "J5") (pin "6") (pinfunction "6_6") (pintype "passive"))
      (node (ref "P7") (pin "1") (pinfunction "1_1") (pintype "passive"))
    )
    (net (code "80") (name "P3V3D") (class "Default")
      (node (ref "C3") (pin "2") (pinfunction "2_2") (pintype "passive"))
      (node (ref "C4") (pin "2") (pinfunction "2_2") (pintype "passive"))
      (node (ref "C5") (pin "2") (pinfunction "2_2") (pintype "passive"))
      (node (ref "C6") (pin "2") (pinfunction "2_2") (pintype "passive"))
      (node (ref "C7") (pin "2") (pinfunction "2_2") (pintype "passive"))
      (node (ref "C8") (pin "2") (pinfunction "2_2") (pintype "passive"))
      (node (ref "J1") (pin "01") (pinfunction "01_01") (pintype "passive"))
      (node (ref "J5") (pin "1") (pinfunction "1_1") (pintype "passive"))
      (node (ref "P1") (pin "1") (pinfunction "1_1") (pintype "passive"))
      (node (ref "R3") (pin "1") (pinfunction "1_1") (pintype "passive"))
      (node (ref "R4") (pin "2") (pinfunction "2_2") (pintype "passive"))
      (node (ref "R5") (pin "2") (pinfunction "2_2") (pintype "passive"))
      (node (ref "R6") (pin "2") (pinfunction "2_2") (pintype "passive"))
      (node (ref "SB1") (pin "1") (pinfunction "0_1") (pintype "passive"))
      (node (ref "U3") (pin "1") (pinfunction "VDD_REF_1") (pintype "power_in"))
      (node (ref "U3") (pin "12") (pinfunction "VDD_DIFF_12") (pintype "power_in"))
      (node (ref "U3") (pin "17") (pinfunction "VDD_DIFF_17") (pintype "power_in"))
      (node (ref "U3") (pin "21") (pinfunction "VDD_CORE_21") (pintype "power_in"))
      (node (ref "U3") (pin "6") (pinfunction "VDD_DIFF_6") (pintype "power_in"))
    )
    (net (code "81") (name "P5V") (class "Default")
      (node (ref "J1") (pin "03") (pinfunction "03_03") (pintype "passive"))
      (node (ref "J2") (pin "16") (pinfunction "16_16") (pintype "passive"))
      (node (ref "P5") (pin "2") (pinfunction "2_2") (pintype "passive"))
      (node (ref "R1") (pin "1") (pinfunction "1_1") (pintype "passive"))
    )
    (net (code "82") (name "PVDD_1") (class "Default")
      (node (ref "J5") (pin "2") (pinfunction "2_2") (pintype "passive"))
      (node (ref "P1") (pin "2") (pinfunction "2_2") (pintype "passive"))
      (node (ref "P3") (pin "2") (pinfunction "2_2") (pintype "passive"))
      (node (ref "P6") (pin "2") (pinfunction "2_2") (pintype "passive"))
      (node (ref "U4") (pin "2") (pinfunction "VREF1_2") (pintype "power_in"))
    )
    (net (code "83") (name "PVDD_2") (class "Default")
      (node (ref "J5") (pin "4") (pinfunction "4_4") (pintype "passive"))
      (node (ref "P2") (pin "2") (pinfunction "2_2") (pintype "passive"))
    )
    (net (code "84") (name "PVUSBC") (class "Default")
      (node (ref "C2") (pin "2") (pinfunction "2_2") (pintype "passive"))
      (node (ref "P5") (pin "3") (pinfunction "3_3") (pintype "passive"))
      (node (ref "U2") (pin "4") (pinfunction "OUT_1_4") (pintype "output"))
      (node (ref "U2") (pin "5") (pinfunction "OUT_2_5") (pintype "output"))
    )
    (net (code "85") (name "USB_H") (class "Default")
      (node (ref "C1") (pin "2") (pinfunction "2_2") (pintype "passive"))
      (node (ref "J6") (pin "A4") (pinfunction "VBUS_A4") (pintype "passive"))
      (node (ref "J6") (pin "A9") (pinfunction "VBUS_A9") (pintype "passive"))
      (node (ref "U1") (pin "6") (pinfunction "VBUS_6") (pintype "power_in"))
      (node (ref "U2") (pin "1") (pinfunction "IN_1_1") (pintype "power_in"))
      (node (ref "U2") (pin "7") (pinfunction "IN_2_7") (pintype "power_in"))
    )
    (net (code "86") (name "unconnected-(FID1-FID-Pad1)") (class "Default")
      (node (ref "FID1") (pin "1") (pinfunction "FID_1") (pintype "passive"))
    )
    (net (code "87") (name "unconnected-(FID2-FID-Pad1)") (class "Default")
      (node (ref "FID2") (pin "1") (pinfunction "FID_1") (pintype "passive"))
    )
    (net (code "88") (name "unconnected-(FID3-FID-Pad1)") (class "Default")
      (node (ref "FID3") (pin "1") (pinfunction "FID_1") (pintype "passive"))
    )
    (net (code "89") (name "unconnected-(J6-CC2-PadB5)") (class "Default")
      (node (ref "J6") (pin "B5") (pinfunction "CC2_B5") (pintype "passive+no_connect"))
    )
    (net (code "90") (name "unconnected-(J6-Dn2-PadB7)") (class "Default")
      (node (ref "J6") (pin "B7") (pinfunction "Dn2_B7") (pintype "passive+no_connect"))
    )
    (net (code "91") (name "unconnected-(J6-Dp2-PadB6)") (class "Default")
      (node (ref "J6") (pin "B6") (pinfunction "Dp2_B6") (pintype "passive+no_connect"))
    )
    (net (code "92") (name "unconnected-(J6-SBU1-PadA8)") (class "Default")
      (node (ref "J6") (pin "A8") (pinfunction "SBU1_A8") (pintype "passive+no_connect"))
    )
    (net (code "93") (name "unconnected-(J6-SBU2-PadB8)") (class "Default")
      (node (ref "J6") (pin "B8") (pinfunction "SBU2_B8") (pintype "passive+no_connect"))
    )
    (net (code "94") (name "unconnected-(J6-SSRXn2-PadA10)") (class "Default")
      (node (ref "J6") (pin "A10") (pinfunction "SSRXn2_A10") (pintype "passive+no_connect"))
    )
    (net (code "95") (name "unconnected-(J6-SSRXp2-PadA11)") (class "Default")
      (node (ref "J6") (pin "A11") (pinfunction "SSRXp2_A11") (pintype "passive+no_connect"))
    )
    (net (code "96") (name "unconnected-(J6-SSTXn2-PadB3)") (class "Default")
      (node (ref "J6") (pin "B3") (pinfunction "SSTXn2_B3") (pintype "passive+no_connect"))
    )
    (net (code "97") (name "unconnected-(J6-SSTXp2-PadB2)") (class "Default")
      (node (ref "J6") (pin "B2") (pinfunction "SSTXp2_B2") (pintype "passive+no_connect"))
    )
    (net (code "98") (name "unconnected-(J6-VBUS-PadB4)") (class "Default")
      (node (ref "J6") (pin "B4") (pinfunction "VBUS_B4") (pintype "passive"))
    )
    (net (code "99") (name "unconnected-(J6-VBUS-PadB9)") (class "Default")
      (node (ref "J6") (pin "B9") (pinfunction "VBUS_B9") (pintype "passive"))
    )
    (net (code "100") (name "unconnected-(P3-Pad3)") (class "Default")
      (node (ref "P3") (pin "3") (pinfunction "3_3") (pintype "passive"))
    )
    (net (code "101") (name "unconnected-(P3-Pad4)") (class "Default")
      (node (ref "P3") (pin "4") (pinfunction "4_4") (pintype "passive"))
    )
    (net (code "102") (name "unconnected-(P3-Pad5)") (class "Default")
      (node (ref "P3") (pin "5") (pinfunction "5_5") (pintype "passive"))
    )
    (net (code "103") (name "unconnected-(P3-Pad6)") (class "Default")
      (node (ref "P3") (pin "6") (pinfunction "6_6") (pintype "passive"))
    )
    (net (code "104") (name "unconnected-(P3-Pad10)") (class "Default")
      (node (ref "P3") (pin "10") (pinfunction "10_10") (pintype "passive"))
    )
    (net (code "105") (name "unconnected-(P3-Pad11)") (class "Default")
      (node (ref "P3") (pin "11") (pinfunction "11_11") (pintype "passive"))
    )
    (net (code "106") (name "unconnected-(P3-Pad12)") (class "Default")
      (node (ref "P3") (pin "12") (pinfunction "12_12") (pintype "passive"))
    )
    (net (code "107") (name "unconnected-(P4-Pad1)") (class "Default")
      (node (ref "P4") (pin "1") (pinfunction "1_1") (pintype "passive"))
    )
    (net (code "108") (name "unconnected-(P4-Pad2)") (class "Default")
      (node (ref "P4") (pin "2") (pinfunction "2_2") (pintype "passive"))
    )
    (net (code "109") (name "unconnected-(P4-Pad3)") (class "Default")
      (node (ref "P4") (pin "3") (pinfunction "3_3") (pintype "passive"))
    )
    (net (code "110") (name "unconnected-(P4-Pad4)") (class "Default")
      (node (ref "P4") (pin "4") (pinfunction "4_4") (pintype "passive"))
    )
    (net (code "111") (name "unconnected-(P4-Pad5)") (class "Default")
      (node (ref "P4") (pin "5") (pinfunction "5_5") (pintype "passive"))
    )
    (net (code "112") (name "unconnected-(P4-Pad6)") (class "Default")
      (node (ref "P4") (pin "6") (pinfunction "6_6") (pintype "passive"))
    )
    (net (code "113") (name "unconnected-(P4-Pad7)") (class "Default")
      (node (ref "P4") (pin "7") (pinfunction "7_7") (pintype "passive"))
    )
    (net (code "114") (name "unconnected-(P4-Pad8)") (class "Default")
      (node (ref "P4") (pin "8") (pinfunction "8_8") (pintype "passive"))
    )
    (net (code "115") (name "unconnected-(P4-Pad9)") (class "Default")
      (node (ref "P4") (pin "9") (pinfunction "9_9") (pintype "passive"))
    )
    (net (code "116") (name "unconnected-(P4-Pad10)") (class "Default")
      (node (ref "P4") (pin "10") (pinfunction "10_10") (pintype "passive"))
    )
    (net (code "117") (name "unconnected-(P4-Pad11)") (class "Default")
      (node (ref "P4") (pin "11") (pinfunction "11_11") (pintype "passive"))
    )
    (net (code "118") (name "unconnected-(P4-Pad12)") (class "Default")
      (node (ref "P4") (pin "12") (pinfunction "12_12") (pintype "passive"))
    )
    (net (code "119") (name "unconnected-(P4-Pad13)") (class "Default")
      (node (ref "P4") (pin "13") (pinfunction "13_13") (pintype "passive"))
    )
    (net (code "120") (name "unconnected-(P4-Pad17)") (class "Default")
      (node (ref "P4") (pin "17") (pinfunction "17_17") (pintype "passive"))
    )
    (net (code "121") (name "unconnected-(SW1-GND-PadS1)") (class "Default")
      (node (ref "SW1") (pin "S1") (pinfunction "GND_S1") (pintype "passive"))
    )
    (net (code "122") (name "unconnected-(SW2-GND-PadS1)") (class "Default")
      (node (ref "SW2") (pin "S1") (pinfunction "GND_S1") (pintype "passive"))
    )
    (net (code "123") (name "unconnected-(U2-~{FLAG}-Pad3)") (class "Default")
      (node (ref "U2") (pin "3") (pinfunction "~{FLAG}_3") (pintype "output"))
    )
    (net (code "124") (name "unconnected-(U3-NC-Pad9)") (class "Default")
      (node (ref "U3") (pin "9") (pinfunction "NC_9") (pintype "passive"))
    )
    (net (code "125") (name "unconnected-(U3-NC-Pad10)") (class "Default")
      (node (ref "U3") (pin "10") (pinfunction "NC_10") (pintype "passive"))
    )
    (net (code "126") (name "unconnected-(U3-NC-Pad11)") (class "Default")
      (node (ref "U3") (pin "11") (pinfunction "NC_11") (pintype "passive"))
    )
  )
)
